# FGPMMOPA6x.net
KiCad netlist of a schematic drawn in EAGLE
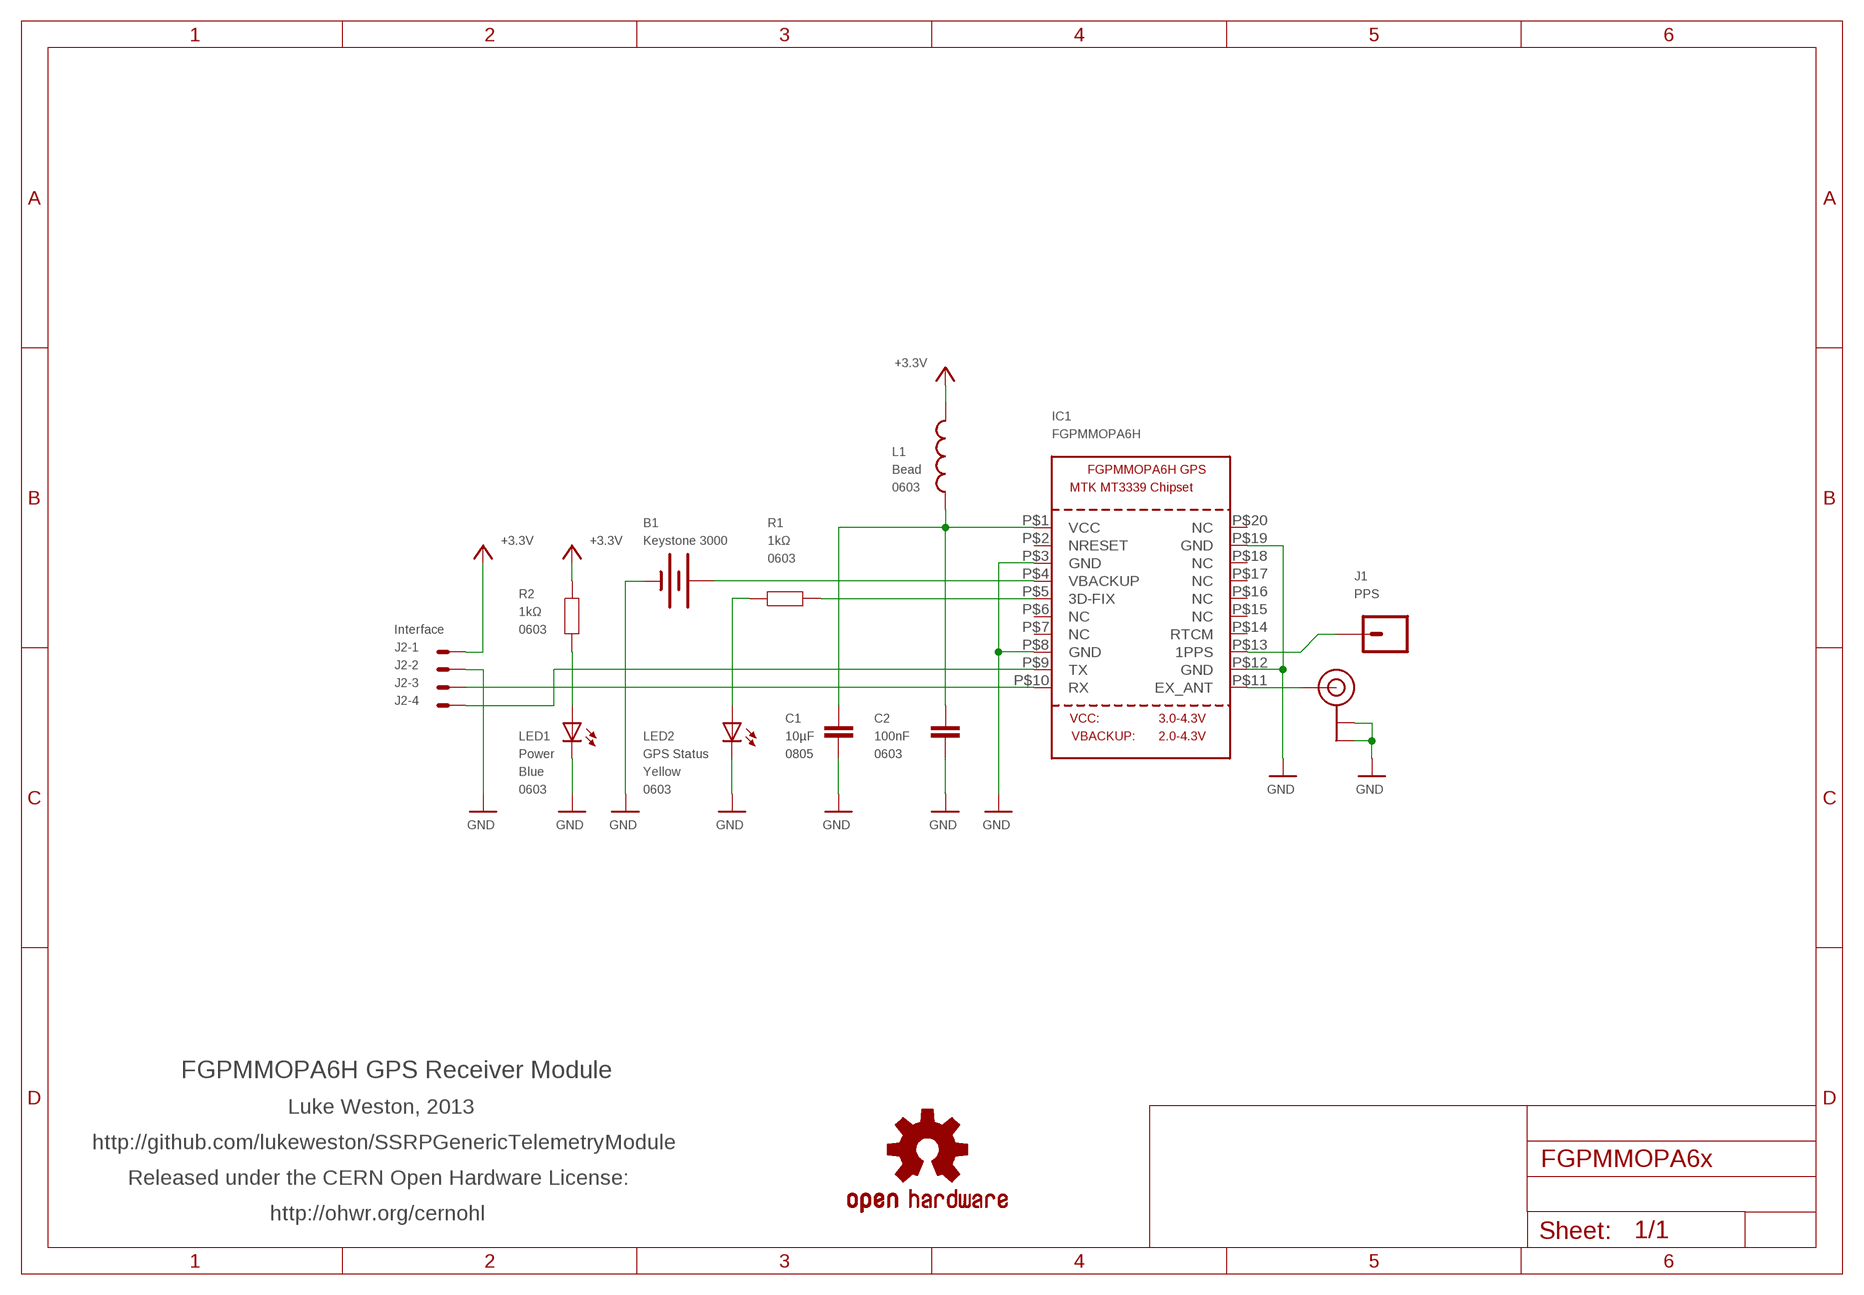
[diagram p0: schematic, sheet 1]

(export (version "E")
  (design (tool "Eeschema 10.0.6"))
  (components
    (comp (ref "B1")
      (value "Keystone 3000")
      (footprint "eagle-import:BATTCON_12MM")
      (libsource (lib "eagle-import") (part "BATTERY12MM"))
    )
    (comp (ref "C1")
      (value "10µF")
      (footprint "eagle-import:0805")
      (fields (field (name "PACKAGE") "0805"))
      (libsource (lib "eagle-import") (part "CAP0805"))
    )
    (comp (ref "C2")
      (value "100nF")
      (footprint "eagle-import:0603")
      (fields (field (name "PACKAGE") "0603"))
      (libsource (lib "eagle-import") (part "CAP0603"))
    )
    (comp (ref "IC1")
      (value "FGPMMOPA6H")
      (footprint "eagle-import:FGPMMOPA6H")
      (libsource (lib "eagle-import") (part "GPS_FGPMMOPA6H"))
    )
    (comp (ref "J1")
      (value "PPS")
      (footprint "eagle-import:1X01")
      (libsource (lib "eagle-import") (part "M01PTH"))
    )
    (comp (ref "J2")
      (value "Interface")
      (footprint "eagle-import:7395-04")
      (fields (field (name "OC_FARNELL") "unknown") (field (name "OC_NEWARK") "unknown"))
      (libsource (lib "eagle-import") (part "22-?-0405-7048"))
    )
    (comp (ref "J3")
      (value "U.FL")
      (footprint "eagle-import:U.FL")
      (libsource (lib "eagle-import") (part "U.FL"))
    )
    (comp (ref "L1")
      (value "Bead")
      (footprint "eagle-import:0603")
      (fields (field (name "PACKAGE") "0603"))
      (libsource (lib "eagle-import") (part "INDUCTOR0603"))
    )
    (comp (ref "LED1")
      (value "Power")
      (footprint "eagle-import:LED-0603")
      (fields (field (name "COLOUR") "Blue") (field (name "PACKAGE") "0603"))
      (libsource (lib "eagle-import") (part "LED0603"))
    )
    (comp (ref "LED2")
      (value "GPS Status")
      (footprint "eagle-import:LED-0603")
      (fields (field (name "COLOUR") "Yellow") (field (name "PACKAGE") "0603"))
      (libsource (lib "eagle-import") (part "LED0603"))
    )
    (comp (ref "R1")
      (value "1kΩ")
      (footprint "eagle-import:0603")
      (fields (field (name "PACKAGE") "0603"))
      (libsource (lib "eagle-import") (part "RESISTOR0603"))
    )
    (comp (ref "R2")
      (value "1kΩ")
      (footprint "eagle-import:0603")
      (fields (field (name "PACKAGE") "0603"))
      (libsource (lib "eagle-import") (part "RESISTOR0603"))
    )
    (comp (ref "SY2")
      (value "OSHW-LOGOS")
      (footprint "eagle-import:OSHW-LOGO-S")
      (libsource (lib "eagle-import") (part "OSHW-LOGOS"))
    )
  )
  (nets
    (net (code "1") (name "+3.3V") (class "Default")
      (node (ref "J2") (pin "1") (pinfunction "S_1") (pintype "passive"))
      (node (ref "L1") (pin "2") (pinfunction "2_2") (pintype "passive"))
      (node (ref "R2") (pin "2") (pinfunction "2_2") (pintype "passive"))
    )
    (net (code "2") (name "GND") (class "Default")
      (node (ref "B1") (pin "GND") (pinfunction "-_GND") (pintype "power_in"))
      (node (ref "C1") (pin "1") (pinfunction "1_1") (pintype "passive"))
      (node (ref "C2") (pin "1") (pinfunction "1_1") (pintype "passive"))
      (node (ref "IC1") (pin "P$12") (pinfunction "GND_P$12") (pintype "bidirectional"))
      (node (ref "IC1") (pin "P$19") (pinfunction "GND_P$19") (pintype "bidirectional"))
      (node (ref "IC1") (pin "P$3") (pinfunction "GND_P$3") (pintype "bidirectional"))
      (node (ref "IC1") (pin "P$8") (pinfunction "GND_P$8") (pintype "bidirectional"))
      (node (ref "J2") (pin "2") (pinfunction "S_2") (pintype "passive"))
      (node (ref "J3") (pin "P$1") (pinfunction "GND_P$1") (pintype "bidirectional"))
      (node (ref "J3") (pin "P$2") (pinfunction "GND_P$2") (pintype "bidirectional"))
      (node (ref "LED1") (pin "C") (pinfunction "C_C") (pintype "passive"))
      (node (ref "LED2") (pin "C") (pinfunction "C_C") (pintype "passive"))
    )
    (net (code "3") (name "Net-(B1-+)") (class "Default")
      (node (ref "B1") (pin "PWR@1") (pinfunction "+_PWR@1") (pintype "power_in"))
      (node (ref "IC1") (pin "P$4") (pinfunction "VBACKUP_P$4") (pintype "bidirectional"))
    )
    (net (code "4") (name "Net-(IC1-1PPS)") (class "Default")
      (node (ref "IC1") (pin "P$13") (pinfunction "1PPS_P$13") (pintype "bidirectional"))
      (node (ref "J1") (pin "1") (pinfunction "1_1") (pintype "passive"))
    )
    (net (code "5") (name "Net-(IC1-3D-FIX)") (class "Default")
      (node (ref "IC1") (pin "P$5") (pinfunction "3D-FIX_P$5") (pintype "bidirectional"))
      (node (ref "R1") (pin "2") (pinfunction "2_2") (pintype "passive"))
    )
    (net (code "6") (name "Net-(IC1-EX_ANT)") (class "Default")
      (node (ref "IC1") (pin "P$11") (pinfunction "EX_ANT_P$11") (pintype "bidirectional"))
      (node (ref "J3") (pin "P$3") (pinfunction "SIGNAL_P$3") (pintype "bidirectional"))
    )
    (net (code "7") (name "Net-(IC1-RX)") (class "Default")
      (node (ref "IC1") (pin "P$10") (pinfunction "RX_P$10") (pintype "bidirectional"))
      (node (ref "J2") (pin "3") (pinfunction "S_3") (pintype "passive"))
    )
    (net (code "8") (name "Net-(IC1-TX)") (class "Default")
      (node (ref "IC1") (pin "P$9") (pinfunction "TX_P$9") (pintype "bidirectional"))
      (node (ref "J2") (pin "4") (pinfunction "S_4") (pintype "passive"))
    )
    (net (code "9") (name "Net-(IC1-VCC)") (class "Default")
      (node (ref "C1") (pin "2") (pinfunction "2_2") (pintype "passive"))
      (node (ref "C2") (pin "2") (pinfunction "2_2") (pintype "passive"))
      (node (ref "IC1") (pin "P$1") (pinfunction "VCC_P$1") (pintype "bidirectional"))
      (node (ref "L1") (pin "1") (pinfunction "1_1") (pintype "passive"))
    )
    (net (code "10") (name "Net-(LED1-PadA)") (class "Default")
      (node (ref "LED1") (pin "A") (pinfunction "A_A") (pintype "passive"))
      (node (ref "R2") (pin "1") (pinfunction "1_1") (pintype "passive"))
    )
    (net (code "11") (name "Net-(LED2-PadA)") (class "Default")
      (node (ref "LED2") (pin "A") (pinfunction "A_A") (pintype "passive"))
      (node (ref "R1") (pin "1") (pinfunction "1_1") (pintype "passive"))
    )
    (net (code "12") (name "unconnected-(IC1-NC-PadP$6)") (class "Default")
      (node (ref "IC1") (pin "P$6") (pinfunction "NC_P$6") (pintype "bidirectional"))
    )
    (net (code "13") (name "unconnected-(IC1-NC-PadP$7)") (class "Default")
      (node (ref "IC1") (pin "P$7") (pinfunction "NC_P$7") (pintype "bidirectional"))
    )
    (net (code "14") (name "unconnected-(IC1-NC-PadP$15)") (class "Default")
      (node (ref "IC1") (pin "P$15") (pinfunction "NC_P$15") (pintype "bidirectional"))
    )
    (net (code "15") (name "unconnected-(IC1-NC-PadP$16)") (class "Default")
      (node (ref "IC1") (pin "P$16") (pinfunction "NC_P$16") (pintype "bidirectional"))
    )
    (net (code "16") (name "unconnected-(IC1-NC-PadP$17)") (class "Default")
      (node (ref "IC1") (pin "P$17") (pinfunction "NC_P$17") (pintype "bidirectional"))
    )
    (net (code "17") (name "unconnected-(IC1-NC-PadP$18)") (class "Default")
      (node (ref "IC1") (pin "P$18") (pinfunction "NC_P$18") (pintype "bidirectional"))
    )
    (net (code "18") (name "unconnected-(IC1-NC-PadP$20)") (class "Default")
      (node (ref "IC1") (pin "P$20") (pinfunction "NC_P$20") (pintype "bidirectional"))
    )
    (net (code "19") (name "unconnected-(IC1-NRESET-PadP$2)") (class "Default")
      (node (ref "IC1") (pin "P$2") (pinfunction "NRESET_P$2") (pintype "bidirectional"))
    )
    (net (code "20") (name "unconnected-(IC1-RTCM-PadP$14)") (class "Default")
      (node (ref "IC1") (pin "P$14") (pinfunction "RTCM_P$14") (pintype "bidirectional"))
    )
  )
)
